# HPC_AB.net
KiCad netlist of a schematic drawn in Altium Designer
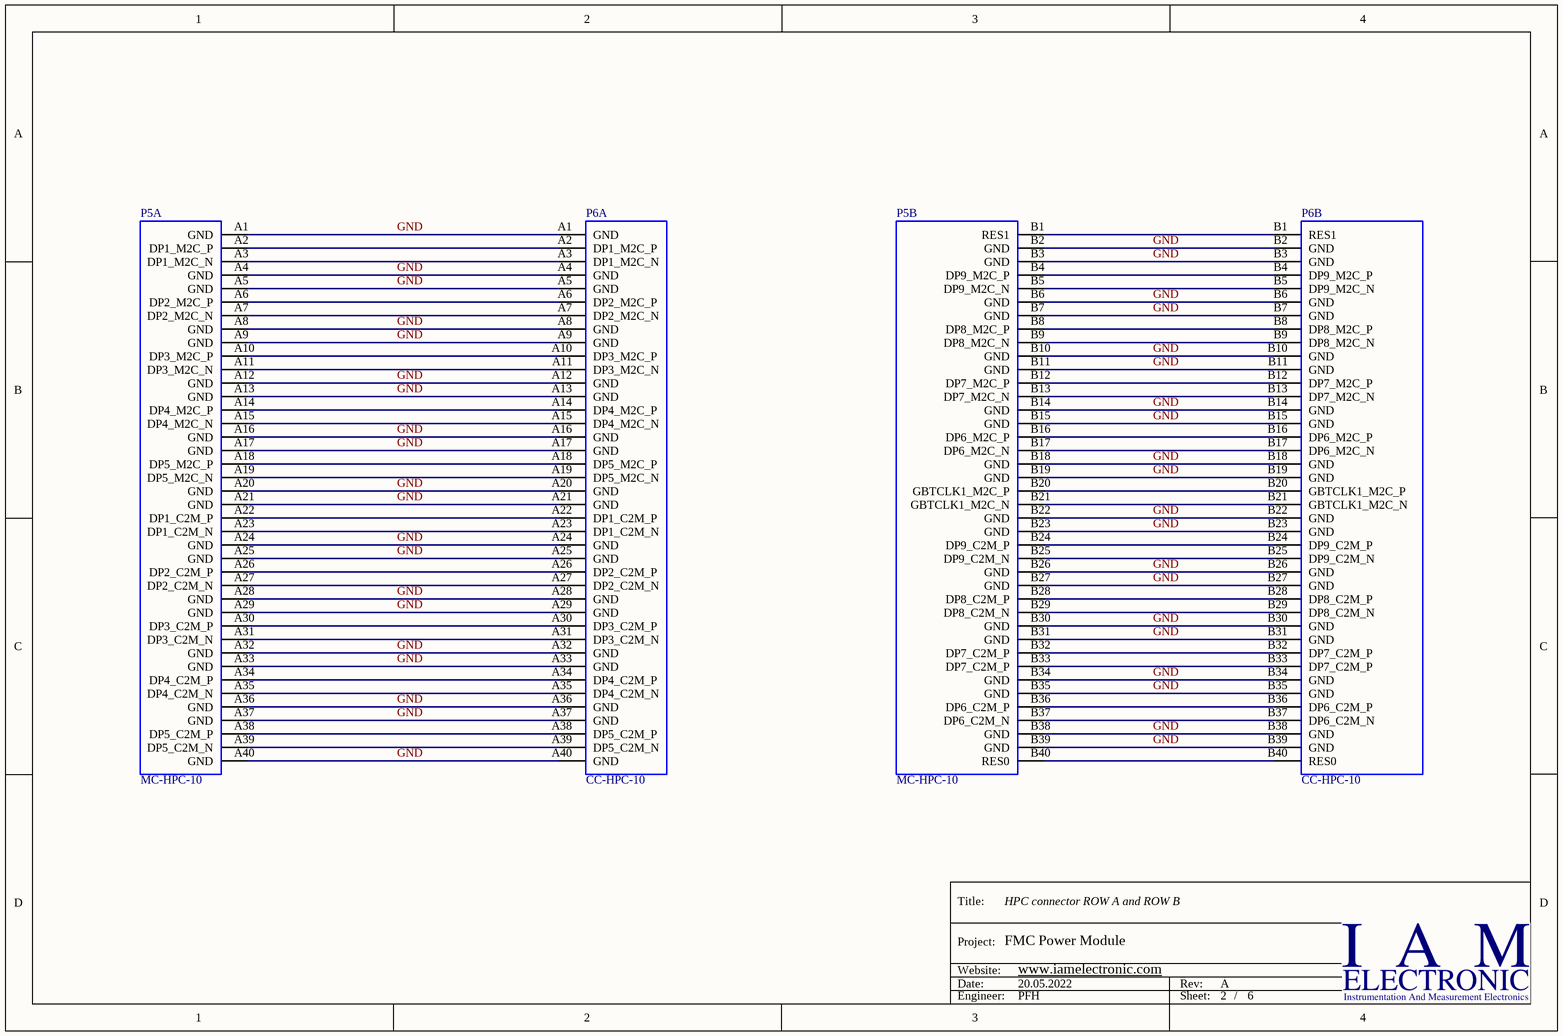
[diagram p0: HPC_AB.SchDoc]

(export (version "E")
  (design (tool "Eeschema 10.0.6"))
  (components
    (comp (ref "P5")
      (value "MC-HPC-10")
      (footprint "ASP-134488-01")
      (description "MC-HPC-10, FMC High-pin count connector, lead free, 400 I/Os, male, 10 mm mated stack height")
      (fields (field (name "MANUFACTURER") "Samtec") (field (name "PART") "ASP-134488-01"))
      (libsource (lib "VITA_57_FMC") (part "MC-HPC-10"))
    )
    (comp (ref "P6")
      (value "CC-HPC-10")
      (footprint "ASP-134486-01")
      (description "CC-HPC-10, FMC High-pin count connector, lead free, 400 I/Os, female, 10 mm mated stack height")
      (fields (field (name "MANUFACTURER") "Samtec") (field (name "PART") "ASP-134486-01"))
      (libsource (lib "VITA_57_FMC") (part "CC-HPC-10"))
    )
  )
  (nets
    (net (code "1") (name "/GND") (class "Default")
      (node (ref "P5") (pin "A1") (pinfunction "GND_A1") (pintype "passive"))
      (node (ref "P5") (pin "A12") (pinfunction "GND_A12") (pintype "passive"))
      (node (ref "P5") (pin "A13") (pinfunction "GND_A13") (pintype "passive"))
      (node (ref "P5") (pin "A16") (pinfunction "GND_A16") (pintype "passive"))
      (node (ref "P5") (pin "A17") (pinfunction "GND_A17") (pintype "passive"))
      (node (ref "P5") (pin "A20") (pinfunction "GND_A20") (pintype "passive"))
      (node (ref "P5") (pin "A21") (pinfunction "GND_A21") (pintype "passive"))
      (node (ref "P5") (pin "A24") (pinfunction "GND_A24") (pintype "passive"))
      (node (ref "P5") (pin "A25") (pinfunction "GND_A25") (pintype "passive"))
      (node (ref "P5") (pin "A28") (pinfunction "GND_A28") (pintype "passive"))
      (node (ref "P5") (pin "A29") (pinfunction "GND_A29") (pintype "passive"))
      (node (ref "P5") (pin "A32") (pinfunction "GND_A32") (pintype "passive"))
      (node (ref "P5") (pin "A33") (pinfunction "GND_A33") (pintype "passive"))
      (node (ref "P5") (pin "A36") (pinfunction "GND_A36") (pintype "passive"))
      (node (ref "P5") (pin "A37") (pinfunction "GND_A37") (pintype "passive"))
      (node (ref "P5") (pin "A4") (pinfunction "GND_A4") (pintype "passive"))
      (node (ref "P5") (pin "A40") (pinfunction "GND_A40") (pintype "passive"))
      (node (ref "P5") (pin "A5") (pinfunction "GND_A5") (pintype "passive"))
      (node (ref "P5") (pin "A8") (pinfunction "GND_A8") (pintype "passive"))
      (node (ref "P5") (pin "A9") (pinfunction "GND_A9") (pintype "passive"))
      (node (ref "P5") (pin "B10") (pinfunction "GND_B10") (pintype "passive"))
      (node (ref "P5") (pin "B11") (pinfunction "GND_B11") (pintype "passive"))
      (node (ref "P5") (pin "B14") (pinfunction "GND_B14") (pintype "passive"))
      (node (ref "P5") (pin "B15") (pinfunction "GND_B15") (pintype "passive"))
      (node (ref "P5") (pin "B18") (pinfunction "GND_B18") (pintype "passive"))
      (node (ref "P5") (pin "B19") (pinfunction "GND_B19") (pintype "passive"))
      (node (ref "P5") (pin "B2") (pinfunction "GND_B2") (pintype "passive"))
      (node (ref "P5") (pin "B22") (pinfunction "GND_B22") (pintype "passive"))
      (node (ref "P5") (pin "B23") (pinfunction "GND_B23") (pintype "passive"))
      (node (ref "P5") (pin "B26") (pinfunction "GND_B26") (pintype "passive"))
      (node (ref "P5") (pin "B27") (pinfunction "GND_B27") (pintype "passive"))
      (node (ref "P5") (pin "B3") (pinfunction "GND_B3") (pintype "passive"))
      (node (ref "P5") (pin "B30") (pinfunction "GND_B30") (pintype "passive"))
      (node (ref "P5") (pin "B31") (pinfunction "GND_B31") (pintype "passive"))
      (node (ref "P5") (pin "B34") (pinfunction "GND_B34") (pintype "passive"))
      (node (ref "P5") (pin "B35") (pinfunction "GND_B35") (pintype "passive"))
      (node (ref "P5") (pin "B38") (pinfunction "GND_B38") (pintype "passive"))
      (node (ref "P5") (pin "B39") (pinfunction "GND_B39") (pintype "passive"))
      (node (ref "P5") (pin "B6") (pinfunction "GND_B6") (pintype "passive"))
      (node (ref "P5") (pin "B7") (pinfunction "GND_B7") (pintype "passive"))
      (node (ref "P6") (pin "A1") (pinfunction "GND_A1") (pintype "passive"))
      (node (ref "P6") (pin "A12") (pinfunction "GND_A12") (pintype "passive"))
      (node (ref "P6") (pin "A13") (pinfunction "GND_A13") (pintype "passive"))
      (node (ref "P6") (pin "A16") (pinfunction "GND_A16") (pintype "passive"))
      (node (ref "P6") (pin "A17") (pinfunction "GND_A17") (pintype "passive"))
      (node (ref "P6") (pin "A20") (pinfunction "GND_A20") (pintype "passive"))
      (node (ref "P6") (pin "A21") (pinfunction "GND_A21") (pintype "passive"))
      (node (ref "P6") (pin "A24") (pinfunction "GND_A24") (pintype "passive"))
      (node (ref "P6") (pin "A25") (pinfunction "GND_A25") (pintype "passive"))
      (node (ref "P6") (pin "A28") (pinfunction "GND_A28") (pintype "passive"))
      (node (ref "P6") (pin "A29") (pinfunction "GND_A29") (pintype "passive"))
      (node (ref "P6") (pin "A32") (pinfunction "GND_A32") (pintype "passive"))
      (node (ref "P6") (pin "A33") (pinfunction "GND_A33") (pintype "passive"))
      (node (ref "P6") (pin "A36") (pinfunction "GND_A36") (pintype "passive"))
      (node (ref "P6") (pin "A37") (pinfunction "GND_A37") (pintype "passive"))
      (node (ref "P6") (pin "A4") (pinfunction "GND_A4") (pintype "passive"))
      (node (ref "P6") (pin "A40") (pinfunction "GND_A40") (pintype "passive"))
      (node (ref "P6") (pin "A5") (pinfunction "GND_A5") (pintype "passive"))
      (node (ref "P6") (pin "A8") (pinfunction "GND_A8") (pintype "passive"))
      (node (ref "P6") (pin "A9") (pinfunction "GND_A9") (pintype "passive"))
      (node (ref "P6") (pin "B10") (pinfunction "GND_B10") (pintype "passive"))
      (node (ref "P6") (pin "B11") (pinfunction "GND_B11") (pintype "passive"))
      (node (ref "P6") (pin "B14") (pinfunction "GND_B14") (pintype "passive"))
      (node (ref "P6") (pin "B15") (pinfunction "GND_B15") (pintype "passive"))
      (node (ref "P6") (pin "B18") (pinfunction "GND_B18") (pintype "passive"))
      (node (ref "P6") (pin "B19") (pinfunction "GND_B19") (pintype "passive"))
      (node (ref "P6") (pin "B2") (pinfunction "GND_B2") (pintype "passive"))
      (node (ref "P6") (pin "B22") (pinfunction "GND_B22") (pintype "passive"))
      (node (ref "P6") (pin "B23") (pinfunction "GND_B23") (pintype "passive"))
      (node (ref "P6") (pin "B26") (pinfunction "GND_B26") (pintype "passive"))
      (node (ref "P6") (pin "B27") (pinfunction "GND_B27") (pintype "passive"))
      (node (ref "P6") (pin "B3") (pinfunction "GND_B3") (pintype "passive"))
      (node (ref "P6") (pin "B30") (pinfunction "GND_B30") (pintype "passive"))
      (node (ref "P6") (pin "B31") (pinfunction "GND_B31") (pintype "passive"))
      (node (ref "P6") (pin "B34") (pinfunction "GND_B34") (pintype "passive"))
      (node (ref "P6") (pin "B35") (pinfunction "GND_B35") (pintype "passive"))
      (node (ref "P6") (pin "B38") (pinfunction "GND_B38") (pintype "passive"))
      (node (ref "P6") (pin "B39") (pinfunction "GND_B39") (pintype "passive"))
      (node (ref "P6") (pin "B6") (pinfunction "GND_B6") (pintype "passive"))
      (node (ref "P6") (pin "B7") (pinfunction "GND_B7") (pintype "passive"))
    )
    (net (code "2") (name "Net-(P5A-DP1_C2M_N)") (class "Default")
      (node (ref "P5") (pin "A23") (pinfunction "DP1_C2M_N_A23") (pintype "passive"))
      (node (ref "P6") (pin "A23") (pinfunction "DP1_C2M_N_A23") (pintype "passive"))
    )
    (net (code "3") (name "Net-(P5A-DP1_C2M_P)") (class "Default")
      (node (ref "P5") (pin "A22") (pinfunction "DP1_C2M_P_A22") (pintype "passive"))
      (node (ref "P6") (pin "A22") (pinfunction "DP1_C2M_P_A22") (pintype "passive"))
    )
    (net (code "4") (name "Net-(P5A-DP1_M2C_N)") (class "Default")
      (node (ref "P5") (pin "A3") (pinfunction "DP1_M2C_N_A3") (pintype "passive"))
      (node (ref "P6") (pin "A3") (pinfunction "DP1_M2C_N_A3") (pintype "passive"))
    )
    (net (code "5") (name "Net-(P5A-DP1_M2C_P)") (class "Default")
      (node (ref "P5") (pin "A2") (pinfunction "DP1_M2C_P_A2") (pintype "passive"))
      (node (ref "P6") (pin "A2") (pinfunction "DP1_M2C_P_A2") (pintype "passive"))
    )
    (net (code "6") (name "Net-(P5A-DP2_C2M_N)") (class "Default")
      (node (ref "P5") (pin "A27") (pinfunction "DP2_C2M_N_A27") (pintype "passive"))
      (node (ref "P6") (pin "A27") (pinfunction "DP2_C2M_N_A27") (pintype "passive"))
    )
    (net (code "7") (name "Net-(P5A-DP2_C2M_P)") (class "Default")
      (node (ref "P5") (pin "A26") (pinfunction "DP2_C2M_P_A26") (pintype "passive"))
      (node (ref "P6") (pin "A26") (pinfunction "DP2_C2M_P_A26") (pintype "passive"))
    )
    (net (code "8") (name "Net-(P5A-DP2_M2C_N)") (class "Default")
      (node (ref "P5") (pin "A7") (pinfunction "DP2_M2C_N_A7") (pintype "passive"))
      (node (ref "P6") (pin "A7") (pinfunction "DP2_M2C_N_A7") (pintype "passive"))
    )
    (net (code "9") (name "Net-(P5A-DP2_M2C_P)") (class "Default")
      (node (ref "P5") (pin "A6") (pinfunction "DP2_M2C_P_A6") (pintype "passive"))
      (node (ref "P6") (pin "A6") (pinfunction "DP2_M2C_P_A6") (pintype "passive"))
    )
    (net (code "10") (name "Net-(P5A-DP3_C2M_N)") (class "Default")
      (node (ref "P5") (pin "A31") (pinfunction "DP3_C2M_N_A31") (pintype "passive"))
      (node (ref "P6") (pin "A31") (pinfunction "DP3_C2M_N_A31") (pintype "passive"))
    )
    (net (code "11") (name "Net-(P5A-DP3_C2M_P)") (class "Default")
      (node (ref "P5") (pin "A30") (pinfunction "DP3_C2M_P_A30") (pintype "passive"))
      (node (ref "P6") (pin "A30") (pinfunction "DP3_C2M_P_A30") (pintype "passive"))
    )
    (net (code "12") (name "Net-(P5A-DP3_M2C_N)") (class "Default")
      (node (ref "P5") (pin "A11") (pinfunction "DP3_M2C_N_A11") (pintype "passive"))
      (node (ref "P6") (pin "A11") (pinfunction "DP3_M2C_N_A11") (pintype "passive"))
    )
    (net (code "13") (name "Net-(P5A-DP3_M2C_P)") (class "Default")
      (node (ref "P5") (pin "A10") (pinfunction "DP3_M2C_P_A10") (pintype "passive"))
      (node (ref "P6") (pin "A10") (pinfunction "DP3_M2C_P_A10") (pintype "passive"))
    )
    (net (code "14") (name "Net-(P5A-DP4_C2M_N)") (class "Default")
      (node (ref "P5") (pin "A35") (pinfunction "DP4_C2M_N_A35") (pintype "passive"))
      (node (ref "P6") (pin "A35") (pinfunction "DP4_C2M_N_A35") (pintype "passive"))
    )
    (net (code "15") (name "Net-(P5A-DP4_C2M_P)") (class "Default")
      (node (ref "P5") (pin "A34") (pinfunction "DP4_C2M_P_A34") (pintype "passive"))
      (node (ref "P6") (pin "A34") (pinfunction "DP4_C2M_P_A34") (pintype "passive"))
    )
    (net (code "16") (name "Net-(P5A-DP4_M2C_N)") (class "Default")
      (node (ref "P5") (pin "A15") (pinfunction "DP4_M2C_N_A15") (pintype "passive"))
      (node (ref "P6") (pin "A15") (pinfunction "DP4_M2C_N_A15") (pintype "passive"))
    )
    (net (code "17") (name "Net-(P5A-DP4_M2C_P)") (class "Default")
      (node (ref "P5") (pin "A14") (pinfunction "DP4_M2C_P_A14") (pintype "passive"))
      (node (ref "P6") (pin "A14") (pinfunction "DP4_M2C_P_A14") (pintype "passive"))
    )
    (net (code "18") (name "Net-(P5A-DP5_C2M_N)") (class "Default")
      (node (ref "P5") (pin "A39") (pinfunction "DP5_C2M_N_A39") (pintype "passive"))
      (node (ref "P6") (pin "A39") (pinfunction "DP5_C2M_N_A39") (pintype "passive"))
    )
    (net (code "19") (name "Net-(P5A-DP5_C2M_P)") (class "Default")
      (node (ref "P5") (pin "A38") (pinfunction "DP5_C2M_P_A38") (pintype "passive"))
      (node (ref "P6") (pin "A38") (pinfunction "DP5_C2M_P_A38") (pintype "passive"))
    )
    (net (code "20") (name "Net-(P5A-DP5_M2C_N)") (class "Default")
      (node (ref "P5") (pin "A19") (pinfunction "DP5_M2C_N_A19") (pintype "passive"))
      (node (ref "P6") (pin "A19") (pinfunction "DP5_M2C_N_A19") (pintype "passive"))
    )
    (net (code "21") (name "Net-(P5A-DP5_M2C_P)") (class "Default")
      (node (ref "P5") (pin "A18") (pinfunction "DP5_M2C_P_A18") (pintype "passive"))
      (node (ref "P6") (pin "A18") (pinfunction "DP5_M2C_P_A18") (pintype "passive"))
    )
    (net (code "22") (name "Net-(P5B-DP6_C2M_N)") (class "Default")
      (node (ref "P5") (pin "B37") (pinfunction "DP6_C2M_N_B37") (pintype "passive"))
      (node (ref "P6") (pin "B37") (pinfunction "DP6_C2M_N_B37") (pintype "passive"))
    )
    (net (code "23") (name "Net-(P5B-DP6_C2M_P)") (class "Default")
      (node (ref "P5") (pin "B36") (pinfunction "DP6_C2M_P_B36") (pintype "passive"))
      (node (ref "P6") (pin "B36") (pinfunction "DP6_C2M_P_B36") (pintype "passive"))
    )
    (net (code "24") (name "Net-(P5B-DP6_M2C_N)") (class "Default")
      (node (ref "P5") (pin "B17") (pinfunction "DP6_M2C_N_B17") (pintype "passive"))
      (node (ref "P6") (pin "B17") (pinfunction "DP6_M2C_N_B17") (pintype "passive"))
    )
    (net (code "25") (name "Net-(P5B-DP6_M2C_P)") (class "Default")
      (node (ref "P5") (pin "B16") (pinfunction "DP6_M2C_P_B16") (pintype "passive"))
      (node (ref "P6") (pin "B16") (pinfunction "DP6_M2C_P_B16") (pintype "passive"))
    )
    (net (code "26") (name "Net-(P5B-DP7_C2M_P-PadB32)") (class "Default")
      (node (ref "P5") (pin "B32") (pinfunction "DP7_C2M_P_B32") (pintype "passive"))
      (node (ref "P6") (pin "B32") (pinfunction "DP7_C2M_P_B32") (pintype "passive"))
    )
    (net (code "27") (name "Net-(P5B-DP7_C2M_P-PadB33)") (class "Default")
      (node (ref "P5") (pin "B33") (pinfunction "DP7_C2M_P_B33") (pintype "passive"))
      (node (ref "P6") (pin "B33") (pinfunction "DP7_C2M_P_B33") (pintype "passive"))
    )
    (net (code "28") (name "Net-(P5B-DP7_M2C_N)") (class "Default")
      (node (ref "P5") (pin "B13") (pinfunction "DP7_M2C_N_B13") (pintype "passive"))
      (node (ref "P6") (pin "B13") (pinfunction "DP7_M2C_N_B13") (pintype "passive"))
    )
    (net (code "29") (name "Net-(P5B-DP7_M2C_P)") (class "Default")
      (node (ref "P5") (pin "B12") (pinfunction "DP7_M2C_P_B12") (pintype "passive"))
      (node (ref "P6") (pin "B12") (pinfunction "DP7_M2C_P_B12") (pintype "passive"))
    )
    (net (code "30") (name "Net-(P5B-DP8_C2M_N)") (class "Default")
      (node (ref "P5") (pin "B29") (pinfunction "DP8_C2M_N_B29") (pintype "passive"))
      (node (ref "P6") (pin "B29") (pinfunction "DP8_C2M_N_B29") (pintype "passive"))
    )
    (net (code "31") (name "Net-(P5B-DP8_C2M_P)") (class "Default")
      (node (ref "P5") (pin "B28") (pinfunction "DP8_C2M_P_B28") (pintype "passive"))
      (node (ref "P6") (pin "B28") (pinfunction "DP8_C2M_P_B28") (pintype "passive"))
    )
    (net (code "32") (name "Net-(P5B-DP8_M2C_N)") (class "Default")
      (node (ref "P5") (pin "B9") (pinfunction "DP8_M2C_N_B9") (pintype "passive"))
      (node (ref "P6") (pin "B9") (pinfunction "DP8_M2C_N_B9") (pintype "passive"))
    )
    (net (code "33") (name "Net-(P5B-DP8_M2C_P)") (class "Default")
      (node (ref "P5") (pin "B8") (pinfunction "DP8_M2C_P_B8") (pintype "passive"))
      (node (ref "P6") (pin "B8") (pinfunction "DP8_M2C_P_B8") (pintype "passive"))
    )
    (net (code "34") (name "Net-(P5B-DP9_C2M_N)") (class "Default")
      (node (ref "P5") (pin "B25") (pinfunction "DP9_C2M_N_B25") (pintype "passive"))
      (node (ref "P6") (pin "B25") (pinfunction "DP9_C2M_N_B25") (pintype "passive"))
    )
    (net (code "35") (name "Net-(P5B-DP9_C2M_P)") (class "Default")
      (node (ref "P5") (pin "B24") (pinfunction "DP9_C2M_P_B24") (pintype "passive"))
      (node (ref "P6") (pin "B24") (pinfunction "DP9_C2M_P_B24") (pintype "passive"))
    )
    (net (code "36") (name "Net-(P5B-DP9_M2C_N)") (class "Default")
      (node (ref "P5") (pin "B5") (pinfunction "DP9_M2C_N_B5") (pintype "passive"))
      (node (ref "P6") (pin "B5") (pinfunction "DP9_M2C_N_B5") (pintype "passive"))
    )
    (net (code "37") (name "Net-(P5B-DP9_M2C_P)") (class "Default")
      (node (ref "P5") (pin "B4") (pinfunction "DP9_M2C_P_B4") (pintype "passive"))
      (node (ref "P6") (pin "B4") (pinfunction "DP9_M2C_P_B4") (pintype "passive"))
    )
    (net (code "38") (name "Net-(P5B-GBTCLK1_M2C_N)") (class "Default")
      (node (ref "P5") (pin "B21") (pinfunction "GBTCLK1_M2C_N_B21") (pintype "passive"))
      (node (ref "P6") (pin "B21") (pinfunction "GBTCLK1_M2C_N_B21") (pintype "passive"))
    )
    (net (code "39") (name "Net-(P5B-GBTCLK1_M2C_P)") (class "Default")
      (node (ref "P5") (pin "B20") (pinfunction "GBTCLK1_M2C_P_B20") (pintype "passive"))
      (node (ref "P6") (pin "B20") (pinfunction "GBTCLK1_M2C_P_B20") (pintype "passive"))
    )
    (net (code "40") (name "Net-(P5B-RES0)") (class "Default")
      (node (ref "P5") (pin "B40") (pinfunction "RES0_B40") (pintype "passive"))
      (node (ref "P6") (pin "B40") (pinfunction "RES0_B40") (pintype "passive"))
    )
    (net (code "41") (name "Net-(P5B-RES1)") (class "Default")
      (node (ref "P5") (pin "B1") (pinfunction "RES1_B1") (pintype "passive"))
      (node (ref "P6") (pin "B1") (pinfunction "RES1_B1") (pintype "passive"))
    )
  )
)
